# SSBtag_ref.net
KiCad netlist of a schematic drawn in Altium Designer
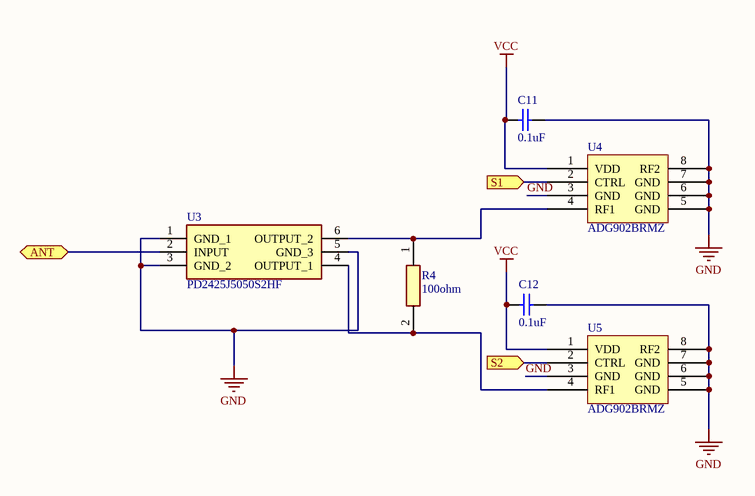
[diagram p0: SSBtag_ref.SchDoc]

(export (version "E")
  (design (tool "Eeschema 10.0.6"))
  (components
    (comp (ref "C11")
      (value "0.1uF")
      (footprint "0402")
      (description "Ceramic Capacitor (Surface Mount)")
      (fields
        (field (name "MANUFACTURER") "Generic Ceramic Chip Cap (TBD)")
        (field (name "Comment") "GCM155R71H104KE02D")
      )
      (libsource (lib "wisp") (part "Cap"))
    )
    (comp (ref "C12")
      (value "0.1uF")
      (footprint "0402")
      (description "Ceramic Capacitor (Surface Mount)")
      (fields
        (field (name "MANUFACTURER") "Generic Ceramic Chip Cap (TBD)")
        (field (name "Comment") "GCM155R71H104KE02D")
      )
      (libsource (lib "wisp") (part "Cap"))
    )
    (comp (ref "R4")
      (value "100ohm")
      (footprint "SamacSys:RESC1608X55N")
      (description "Resistor")
      (fields
        (field (name "MANUFACTURER_PART_NUMBER") "CRCW0603100RFKEAC")
        (field (name "MOUSER PART NUMBER") "71-CRCW0603100RFKEAC")
      )
      (libsource (lib "*") (part "CRCW0603100RFKEAC"))
    )
    (comp (ref "U3")
      (value "PD2425J5050S2HF")
      (footprint "PD2425J5050S2HF")
      (description "Integrated Circuit")
      (fields (field (name "MOUSER PART NUMBER") "620-PD2425J5050S2HF"))
      (libsource (lib "bfp") (part "PD2425J5050S2HF"))
    )
    (comp (ref "U4") (value "ADG902BRMZ") (footprint "ADG902") (libsource (lib "bfp") (part "adg902")))
    (comp (ref "U5") (value "ADG902BRMZ") (footprint "ADG902") (libsource (lib "bfp") (part "adg902")))
  )
  (nets
    (net (code "1") (name "/ANT") (class "Default")
      (node (ref "U3") (pin "2") (pinfunction "INPUT_2") (pintype "passive"))
    )
    (net (code "2") (name "/S1") (class "Default")
      (node (ref "U4") (pin "2") (pinfunction "CTRL_2") (pintype "passive"))
    )
    (net (code "3") (name "/S2") (class "Default")
      (node (ref "U5") (pin "2") (pinfunction "CTRL_2") (pintype "passive"))
    )
    (net (code "4") (name "GND") (class "Default")
      (node (ref "C11") (pin "2") (pinfunction "2_2") (pintype "passive"))
      (node (ref "C12") (pin "2") (pinfunction "2_2") (pintype "passive"))
      (node (ref "U3") (pin "1") (pinfunction "GND_1_1") (pintype "passive"))
      (node (ref "U3") (pin "3") (pinfunction "GND_2_3") (pintype "passive"))
      (node (ref "U3") (pin "5") (pinfunction "GND_3_5") (pintype "passive"))
      (node (ref "U4") (pin "3") (pinfunction "GND_3") (pintype "passive"))
      (node (ref "U4") (pin "5") (pinfunction "GND_5") (pintype "passive"))
      (node (ref "U4") (pin "6") (pinfunction "GND_6") (pintype "passive"))
      (node (ref "U4") (pin "7") (pinfunction "GND_7") (pintype "passive"))
      (node (ref "U4") (pin "8") (pinfunction "RF2_8") (pintype "passive"))
      (node (ref "U5") (pin "3") (pinfunction "GND_3") (pintype "passive"))
      (node (ref "U5") (pin "5") (pinfunction "GND_5") (pintype "passive"))
      (node (ref "U5") (pin "6") (pinfunction "GND_6") (pintype "passive"))
      (node (ref "U5") (pin "7") (pinfunction "GND_7") (pintype "passive"))
      (node (ref "U5") (pin "8") (pinfunction "RF2_8") (pintype "passive"))
    )
    (net (code "5") (name "Net-(U3-OUTPUT_1)") (class "Default")
      (node (ref "R4") (pin "2") (pinfunction "2_2") (pintype "passive"))
      (node (ref "U3") (pin "4") (pinfunction "OUTPUT_1_4") (pintype "passive"))
      (node (ref "U5") (pin "4") (pinfunction "RF1_4") (pintype "passive"))
    )
    (net (code "6") (name "Net-(U3-OUTPUT_2)") (class "Default")
      (node (ref "R4") (pin "1") (pinfunction "1_1") (pintype "passive"))
      (node (ref "U3") (pin "6") (pinfunction "OUTPUT_2_6") (pintype "passive"))
      (node (ref "U4") (pin "4") (pinfunction "RF1_4") (pintype "passive"))
    )
    (net (code "7") (name "VCC") (class "Default")
      (node (ref "C11") (pin "1") (pinfunction "1_1") (pintype "passive"))
      (node (ref "C12") (pin "1") (pinfunction "1_1") (pintype "passive"))
      (node (ref "U4") (pin "1") (pinfunction "VDD_1") (pintype "passive"))
      (node (ref "U5") (pin "1") (pinfunction "VDD_1") (pintype "passive"))
    )
  )
)
